# Power_PMIC.net
KiCad netlist of a schematic drawn in Altium Designer
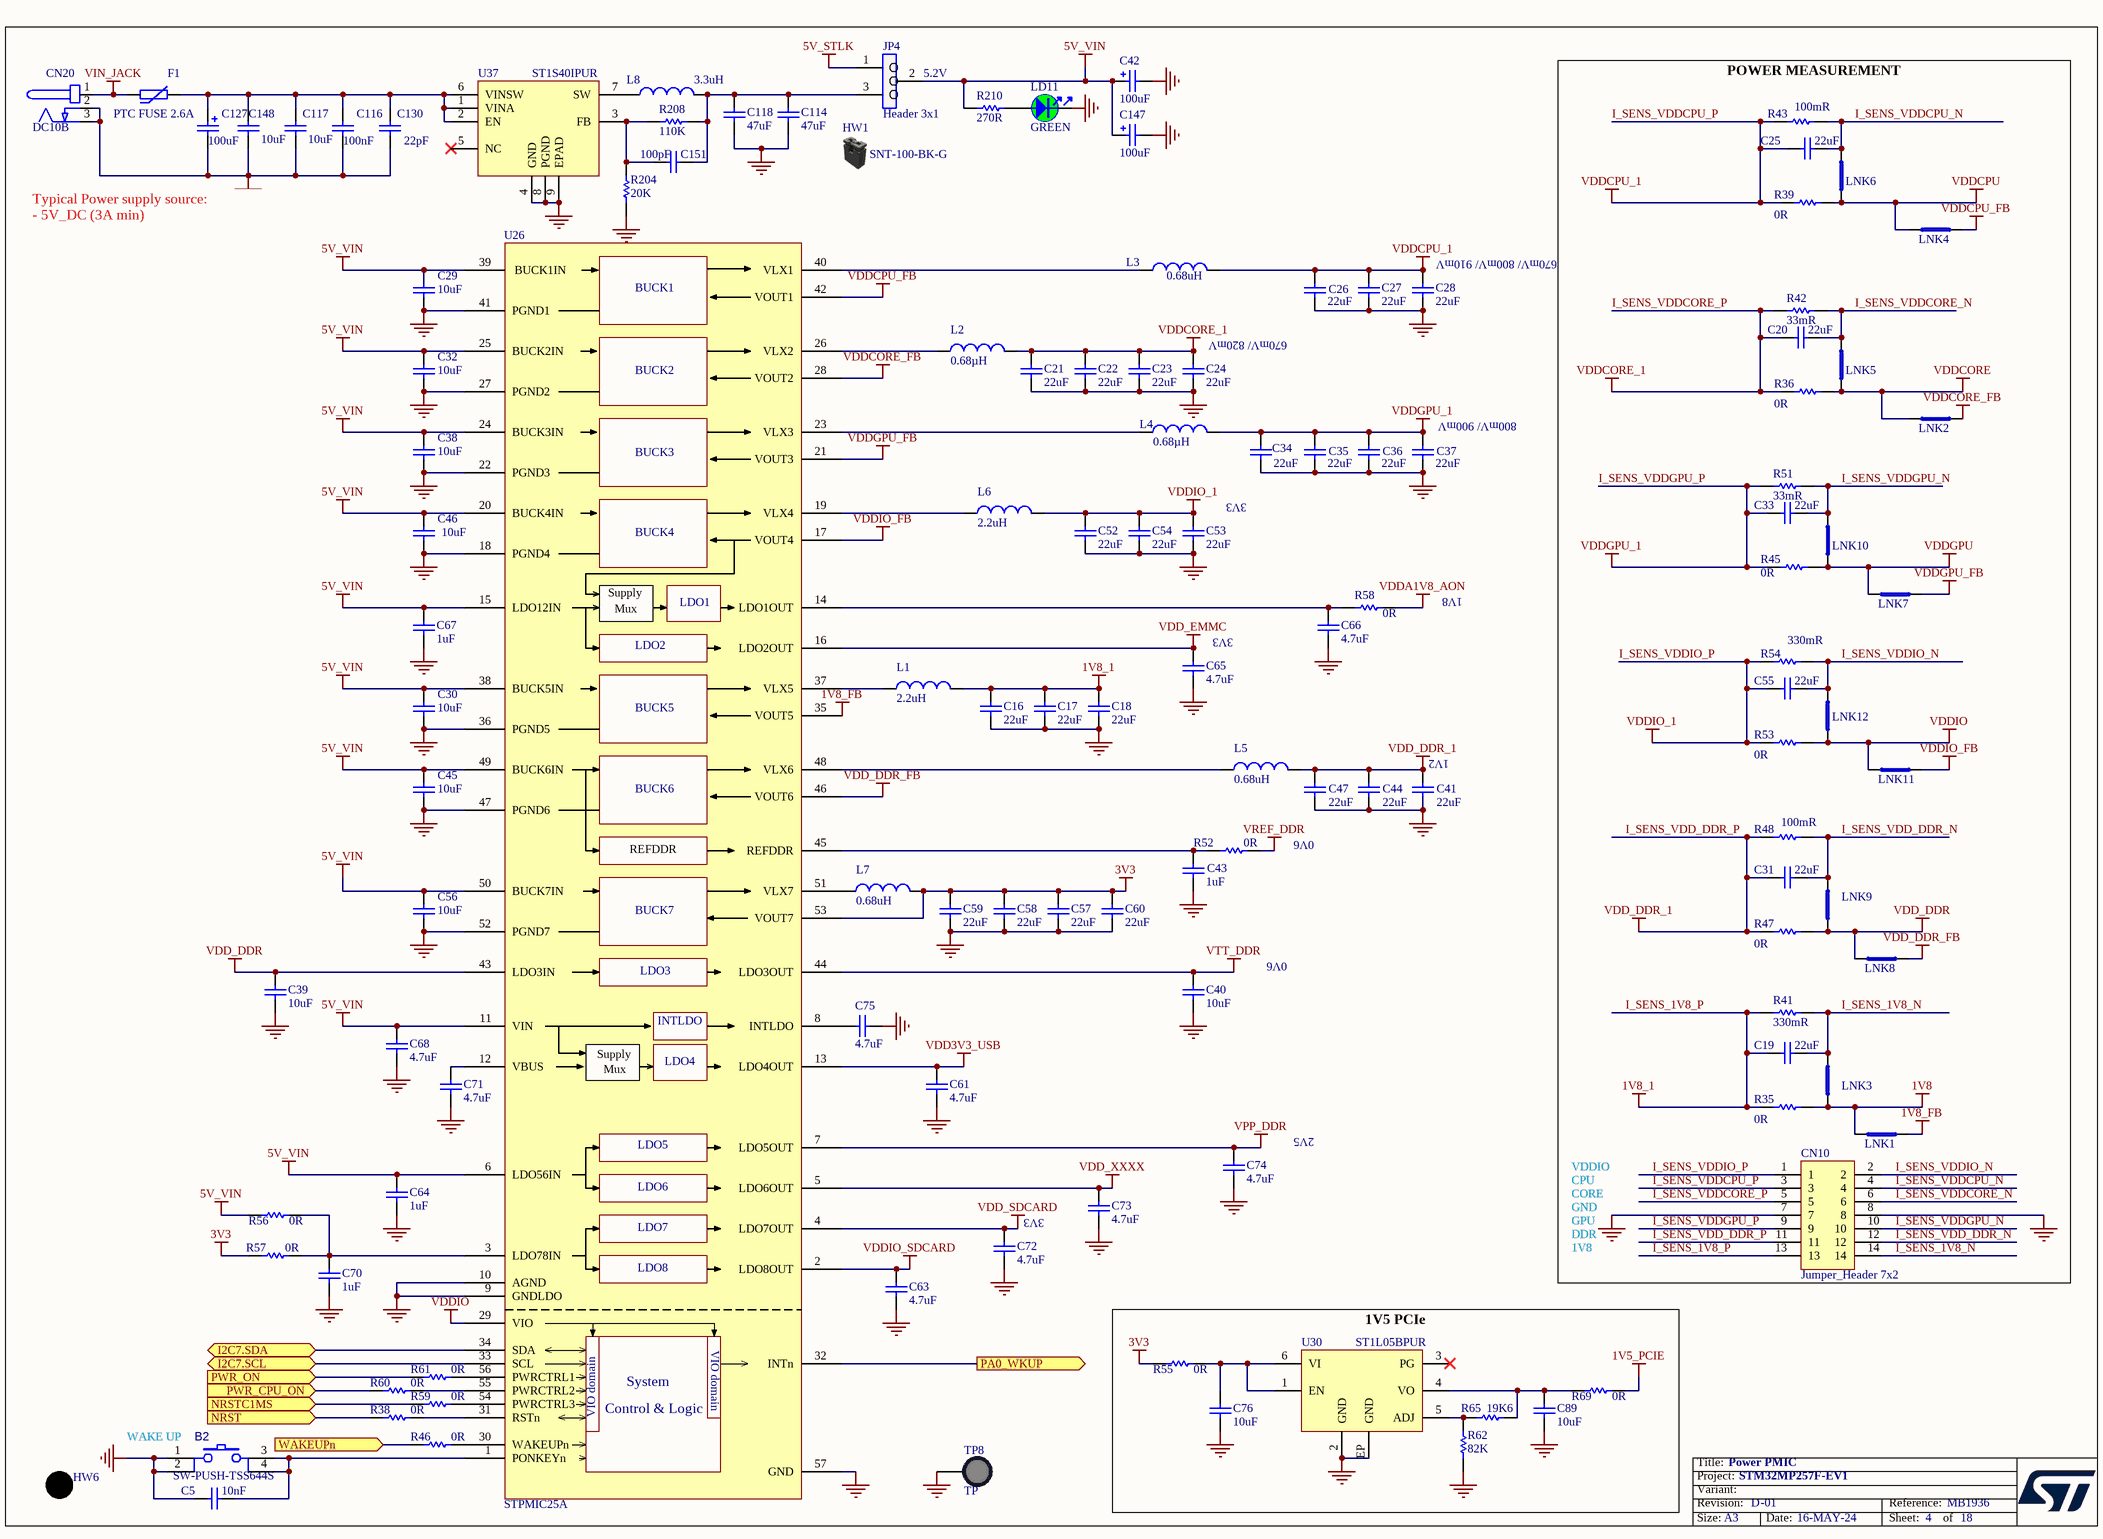
[diagram p0: Power_PMIC.SchDoc]

(export (version "E")
  (design (tool "Eeschema 10.0.6"))
  (components
    (comp (ref "B2")
      (value "SW-PUSH-TSS644S")
      (footprint "MCD_PARTS:SWI_KNITTER_TSS644S")
      (description "Push Button, NO, 0.05A, 12V, 2.6N, SMD, 9.0x6.2mm, T=7.3mm, changeable caps KTSC-6xx")
      (fields
        (field (name "INTERNAL_PART_NUMBER") "MCD-02417")
        (field (name "MANUFACTURER_PART_NUMBER") "TSS644S")
      )
      (libsource (lib "MCD_PARTS_database") (part "SW_PUSH_SMD"))
    )
    (comp (ref "C5")
      (value "10nF")
      (footprint "MCD_PARTS:C0402")
      (description "Capacitor, MLCC, 10nF, 50V, X7R, +/-10%, 0402, T=0.5mm")
      (fields
        (field (name "INTERNAL_PART_NUMBER") "MCD-02198")
        (field (name "MANUFACTURER_PART_NUMBER") "CC0402KRX7R9BB103")
      )
      (libsource (lib "MCD_PARTS_database") (part "Capacitor"))
    )
    (comp (ref "C16")
      (value "22uF")
      (footprint "MCD_PARTS:C0805")
      (description "Capacitor, MLCC, 22uF, 10V, X5R, +/-20%, 0805, T=1,25mm")
      (fields (field (name "INTERNAL_PART_NUMBER") "MCD-03139") (field (name "MANUFACTURER") "MURATA"))
      (libsource (lib "MCD_PARTS_database") (part "Capacitor"))
    )
    (comp (ref "C17")
      (value "22uF")
      (footprint "MCD_PARTS:C0805")
      (description "Capacitor, MLCC, 22uF, 10V, X5R, +/-20%, 0805, T=1,25mm")
      (fields (field (name "INTERNAL_PART_NUMBER") "MCD-03139") (field (name "MANUFACTURER") "MURATA"))
      (libsource (lib "MCD_PARTS_database") (part "Capacitor"))
    )
    (comp (ref "C18")
      (value "22uF")
      (footprint "MCD_PARTS:C0805")
      (description "Capacitor, MLCC, 22uF, 10V, X5R, +/-20%, 0805, T=1,25mm")
      (fields (field (name "INTERNAL_PART_NUMBER") "MCD-03139") (field (name "MANUFACTURER") "MURATA"))
      (libsource (lib "MCD_PARTS_database") (part "Capacitor"))
    )
    (comp (ref "C19")
      (value "22uF")
      (footprint "MCD_PARTS:C0603")
      (description "Capacitor, MLCC, 22uF, 6V3, X5R, +/-20%, 0603, T=0,8mm")
      (fields
        (field (name "INTERNAL_PART_NUMBER") "MCD-00100")
        (field (name "MANUFACTURER_PART_NUMBER") "GRM188R60J226MEA0J")
      )
      (libsource (lib "MCD_PARTS_database") (part "Capacitor"))
    )
    (comp (ref "C20")
      (value "22uF")
      (footprint "MCD_PARTS:C0603")
      (description "Capacitor, MLCC, 22uF, 6V3, X5R, +/-20%, 0603, T=0,8mm")
      (fields
        (field (name "INTERNAL_PART_NUMBER") "MCD-00100")
        (field (name "MANUFACTURER_PART_NUMBER") "GRM188R60J226MEA0J")
      )
      (libsource (lib "MCD_PARTS_database") (part "Capacitor"))
    )
    (comp (ref "C21")
      (value "22uF")
      (footprint "MCD_PARTS:C0603")
      (description "Capacitor, MLCC, 22uF, 6V3, X5R, +/-20%, 0603, T=0,8mm")
      (fields (field (name "INTERNAL_PART_NUMBER") "MCD-00100") (field (name "MANUFACTURER") "MURATA"))
      (libsource (lib "MCD_PARTS_database") (part "Capacitor"))
    )
    (comp (ref "C22")
      (value "22uF")
      (footprint "MCD_PARTS:C0603")
      (description "Capacitor, MLCC, 22uF, 6V3, X5R, +/-20%, 0603, T=0,8mm")
      (fields
        (field (name "INTERNAL_PART_NUMBER") "MCD-00100")
        (field (name "MANUFACTURER_PART_NUMBER") "GRM188R60J226MEA0J")
      )
      (libsource (lib "MCD_PARTS_database") (part "Capacitor"))
    )
    (comp (ref "C23")
      (value "22uF")
      (footprint "MCD_PARTS:C0603")
      (description "Capacitor, MLCC, 22uF, 6V3, X5R, +/-20%, 0603, T=0,8mm")
      (fields
        (field (name "INTERNAL_PART_NUMBER") "MCD-00100")
        (field (name "MANUFACTURER_PART_NUMBER") "GRM188R60J226MEA0J")
      )
      (libsource (lib "MCD_PARTS_database") (part "Capacitor"))
    )
    (comp (ref "C24")
      (value "22uF")
      (footprint "MCD_PARTS:C0603")
      (description "Capacitor, MLCC, 22uF, 6V3, X5R, +/-20%, 0603, T=0,8mm")
      (fields
        (field (name "INTERNAL_PART_NUMBER") "MCD-00100")
        (field (name "MANUFACTURER_PART_NUMBER") "GRM188R60J226MEA0J")
      )
      (libsource (lib "MCD_PARTS_database") (part "Capacitor"))
    )
    (comp (ref "C25")
      (value "22uF")
      (footprint "MCD_PARTS:C0603")
      (description "Capacitor, MLCC, 22uF, 6V3, X5R, +/-20%, 0603, T=0,8mm")
      (fields
        (field (name "INTERNAL_PART_NUMBER") "MCD-00100")
        (field (name "MANUFACTURER_PART_NUMBER") "GRM188R60J226MEA0J")
      )
      (libsource (lib "MCD_PARTS_database") (part "Capacitor"))
    )
    (comp (ref "C26")
      (value "22uF")
      (footprint "MCD_PARTS:C0603")
      (description "Capacitor, MLCC, 22uF, 6V3, X5R, +/-20%, 0603, T=0,8mm")
      (fields
        (field (name "INTERNAL_PART_NUMBER") "MCD-00100")
        (field (name "MANUFACTURER_PART_NUMBER") "GRM188R60J226MEA0J")
      )
      (libsource (lib "MCD_PARTS_database") (part "Capacitor"))
    )
    (comp (ref "C27")
      (value "22uF")
      (footprint "MCD_PARTS:C0603")
      (description "Capacitor, MLCC, 22uF, 6V3, X5R, +/-20%, 0603, T=0,8mm")
      (fields (field (name "INTERNAL_PART_NUMBER") "MCD-00100") (field (name "MANUFACTURER") "MURATA"))
      (libsource (lib "MCD_PARTS_database") (part "Capacitor"))
    )
    (comp (ref "C28")
      (value "22uF")
      (footprint "MCD_PARTS:C0603")
      (description "Capacitor, MLCC, 22uF, 6V3, X5R, +/-20%, 0603, T=0,8mm")
      (fields (field (name "INTERNAL_PART_NUMBER") "MCD-00100") (field (name "MANUFACTURER") "MURATA"))
      (libsource (lib "MCD_PARTS_database") (part "Capacitor"))
    )
    (comp (ref "C29")
      (value "10uF")
      (footprint "MCD_PARTS:C0603")
      (description "Capacitor, MLCC, 10uF, 10V, X5R, +/-10%, 0603, T=0,8mm")
      (fields
        (field (name "INTERNAL_PART_NUMBER") "MCD-00099")
        (field (name "MANUFACTURER_PART_NUMBER") "GRM188R61A106KE69D")
      )
      (libsource (lib "MCD_PARTS_database") (part "Capacitor"))
    )
    (comp (ref "C30")
      (value "10uF")
      (footprint "MCD_PARTS:C0603")
      (description "Capacitor, MLCC, 10uF, 10V, X5R, +/-10%, 0603, T=0,8mm")
      (fields
        (field (name "INTERNAL_PART_NUMBER") "MCD-00099")
        (field (name "MANUFACTURER_PART_NUMBER") "GRM188R61A106KE69D")
      )
      (libsource (lib "MCD_PARTS_database") (part "Capacitor"))
    )
    (comp (ref "C31")
      (value "22uF")
      (footprint "MCD_PARTS:C0603")
      (description "Capacitor, MLCC, 22uF, 6V3, X5R, +/-20%, 0603, T=0,8mm")
      (fields
        (field (name "INTERNAL_PART_NUMBER") "MCD-00100")
        (field (name "MANUFACTURER_PART_NUMBER") "GRM188R60J226MEA0J")
      )
      (libsource (lib "MCD_PARTS_database") (part "Capacitor"))
    )
    (comp (ref "C32")
      (value "10uF")
      (footprint "MCD_PARTS:C0603")
      (description "Capacitor, MLCC, 10uF, 10V, X5R, +/-10%, 0603, T=0,8mm")
      (fields
        (field (name "INTERNAL_PART_NUMBER") "MCD-00099")
        (field (name "MANUFACTURER_PART_NUMBER") "GRM188R61A106KE69D")
      )
      (libsource (lib "MCD_PARTS_database") (part "Capacitor"))
    )
    (comp (ref "C33")
      (value "22uF")
      (footprint "MCD_PARTS:C0603")
      (description "Capacitor, MLCC, 22uF, 6V3, X5R, +/-20%, 0603, T=0,8mm")
      (fields
        (field (name "INTERNAL_PART_NUMBER") "MCD-00100")
        (field (name "MANUFACTURER_PART_NUMBER") "GRM188R60J226MEA0J")
      )
      (libsource (lib "MCD_PARTS_database") (part "Capacitor"))
    )
    (comp (ref "C34")
      (value "22uF")
      (footprint "MCD_PARTS:C0603")
      (description "Capacitor, MLCC, 22uF, 6V3, X5R, +/-20%, 0603, T=0,8mm")
      (fields
        (field (name "INTERNAL_PART_NUMBER") "MCD-00100")
        (field (name "MANUFACTURER_PART_NUMBER") "GRM188R60J226MEA0J")
      )
      (libsource (lib "MCD_PARTS_database") (part "Capacitor"))
    )
    (comp (ref "C35")
      (value "22uF")
      (footprint "MCD_PARTS:C0603")
      (description "Capacitor, MLCC, 22uF, 6V3, X5R, +/-20%, 0603, T=0,8mm")
      (fields
        (field (name "INTERNAL_PART_NUMBER") "MCD-00100")
        (field (name "MANUFACTURER_PART_NUMBER") "GRM188R60J226MEA0J")
      )
      (libsource (lib "MCD_PARTS_database") (part "Capacitor"))
    )
    (comp (ref "C36")
      (value "22uF")
      (footprint "MCD_PARTS:C0603")
      (description "Capacitor, MLCC, 22uF, 6V3, X5R, +/-20%, 0603, T=0,8mm")
      (fields
        (field (name "INTERNAL_PART_NUMBER") "MCD-00100")
        (field (name "MANUFACTURER_PART_NUMBER") "GRM188R60J226MEA0J")
      )
      (libsource (lib "MCD_PARTS_database") (part "Capacitor"))
    )
    (comp (ref "C37")
      (value "22uF")
      (footprint "MCD_PARTS:C0603")
      (description "Capacitor, MLCC, 22uF, 6V3, X5R, +/-20%, 0603, T=0,8mm")
      (fields
        (field (name "INTERNAL_PART_NUMBER") "MCD-00100")
        (field (name "MANUFACTURER_PART_NUMBER") "GRM188R60J226MEA0J")
      )
      (libsource (lib "MCD_PARTS_database") (part "Capacitor"))
    )
    (comp (ref "C38")
      (value "10uF")
      (footprint "MCD_PARTS:C0603")
      (description "Capacitor, MLCC, 10uF, 10V, X5R, +/-10%, 0603, T=0,8mm")
      (fields
        (field (name "INTERNAL_PART_NUMBER") "MCD-00099")
        (field (name "MANUFACTURER_PART_NUMBER") "GRM188R61A106KE69D")
      )
      (libsource (lib "MCD_PARTS_database") (part "Capacitor"))
    )
    (comp (ref "C39")
      (value "10uF")
      (footprint "MCD_PARTS:C0402")
      (description "Capacitor, MLCC, 10uF, 6.3V, X5R, +/-20%, 0402, T=0.5mm")
      (fields (field (name "INTERNAL_PART_NUMBER") "MCD-03140") (field (name "MANUFACTURER") "MURATA"))
      (libsource (lib "MCD_PARTS_database") (part "Capacitor"))
    )
    (comp (ref "C40")
      (value "10uF")
      (footprint "MCD_PARTS:C0402")
      (description "Capacitor, MLCC, 10uF, 6.3V, X5R, +/-20%, 0402, T=0.5mm")
      (fields (field (name "INTERNAL_PART_NUMBER") "MCD-03140") (field (name "MANUFACTURER") "MURATA"))
      (libsource (lib "MCD_PARTS_database") (part "Capacitor"))
    )
    (comp (ref "C41")
      (value "22uF")
      (footprint "MCD_PARTS:C0603")
      (description "Capacitor, MLCC, 22uF, 6V3, X5R, +/-20%, 0603, T=0,8mm")
      (fields
        (field (name "INTERNAL_PART_NUMBER") "MCD-00100")
        (field (name "MANUFACTURER_PART_NUMBER") "GRM188R60J226MEA0J")
      )
      (libsource (lib "MCD_PARTS_database") (part "Capacitor"))
    )
    (comp (ref "C42")
      (value "100uF")
      (footprint "MCD_PARTS:CPOL_TCJ-B_1210_H210")
      (description "Capacitor, Tantalum, 100uF, 6V3, 40mR, +/-20%,  Type_B (3528 metric), T=1.9mm")
      (fields (field (name "INTERNAL_PART_NUMBER") "MCD-01796") (field (name "MANUFACTURER") "AVX"))
      (libsource (lib "MCD_PARTS_database") (part "Cap_POL_TANA"))
    )
    (comp (ref "C43")
      (value "1uF")
      (footprint "MCD_PARTS:C0402")
      (description "Capacitor, MLCC, 1uF, 10V, X5R, +/-10%, 0402, T=0.5mm")
      (fields (field (name "INTERNAL_PART_NUMBER") "MCD-01722") (field (name "MANUFACTURER") "YAGEO"))
      (libsource (lib "MCD_PARTS_database") (part "Capacitor"))
    )
    (comp (ref "C44")
      (value "22uF")
      (footprint "MCD_PARTS:C0603")
      (description "Capacitor, MLCC, 22uF, 6V3, X5R, +/-20%, 0603, T=0,8mm")
      (fields
        (field (name "INTERNAL_PART_NUMBER") "MCD-00100")
        (field (name "MANUFACTURER_PART_NUMBER") "GRM188R60J226MEA0J")
      )
      (libsource (lib "MCD_PARTS_database") (part "Capacitor"))
    )
    (comp (ref "C45")
      (value "10uF")
      (footprint "MCD_PARTS:C0603")
      (description "Capacitor, MLCC, 10uF, 10V, X5R, +/-10%, 0603, T=0,8mm")
      (fields
        (field (name "INTERNAL_PART_NUMBER") "MCD-00099")
        (field (name "MANUFACTURER_PART_NUMBER") "GRM188R61A106KE69D")
      )
      (libsource (lib "MCD_PARTS_database") (part "Capacitor"))
    )
    (comp (ref "C46")
      (value "10uF")
      (footprint "MCD_PARTS:C0603")
      (description "Capacitor, MLCC, 10uF, 10V, X5R, +/-10%, 0603, T=0,8mm")
      (fields
        (field (name "INTERNAL_PART_NUMBER") "MCD-00099")
        (field (name "MANUFACTURER_PART_NUMBER") "GRM188R61A106KE69D")
      )
      (libsource (lib "MCD_PARTS_database") (part "Capacitor"))
    )
    (comp (ref "C47")
      (value "22uF")
      (footprint "MCD_PARTS:C0603")
      (description "Capacitor, MLCC, 22uF, 6V3, X5R, +/-20%, 0603, T=0,8mm")
      (fields
        (field (name "INTERNAL_PART_NUMBER") "MCD-00100")
        (field (name "MANUFACTURER_PART_NUMBER") "GRM188R60J226MEA0J")
      )
      (libsource (lib "MCD_PARTS_database") (part "Capacitor"))
    )
    (comp (ref "C52")
      (value "22uF")
      (footprint "MCD_PARTS:C0805")
      (description "Capacitor, MLCC, 22uF, 10V, X5R, +/-20%, 0805, T=1,25mm")
      (fields (field (name "INTERNAL_PART_NUMBER") "MCD-03139") (field (name "MANUFACTURER") "MURATA"))
      (libsource (lib "MCD_PARTS_database") (part "Capacitor"))
    )
    (comp (ref "C53")
      (value "22uF")
      (footprint "MCD_PARTS:C0805")
      (description "Capacitor, MLCC, 22uF, 10V, X5R, +/-20%, 0805, T=1,25mm")
      (fields (field (name "INTERNAL_PART_NUMBER") "MCD-03139") (field (name "MANUFACTURER") "MURATA"))
      (libsource (lib "MCD_PARTS_database") (part "Capacitor"))
    )
    (comp (ref "C54")
      (value "22uF")
      (footprint "MCD_PARTS:C0805")
      (description "Capacitor, MLCC, 22uF, 10V, X5R, +/-20%, 0805, T=1,25mm")
      (fields (field (name "INTERNAL_PART_NUMBER") "MCD-03139") (field (name "MANUFACTURER") "MURATA"))
      (libsource (lib "MCD_PARTS_database") (part "Capacitor"))
    )
    (comp (ref "C55")
      (value "22uF")
      (footprint "MCD_PARTS:C0603")
      (description "Capacitor, MLCC, 22uF, 6V3, X5R, +/-20%, 0603, T=0,8mm")
      (fields
        (field (name "INTERNAL_PART_NUMBER") "MCD-00100")
        (field (name "MANUFACTURER_PART_NUMBER") "GRM188R60J226MEA0J")
      )
      (libsource (lib "MCD_PARTS_database") (part "Capacitor"))
    )
    (comp (ref "C56")
      (value "10uF")
      (footprint "MCD_PARTS:C0603")
      (description "Capacitor, MLCC, 10uF, 10V, X5R, +/-10%, 0603, T=0,8mm")
      (fields
        (field (name "INTERNAL_PART_NUMBER") "MCD-00099")
        (field (name "MANUFACTURER_PART_NUMBER") "GRM188R61A106KE69D")
      )
      (libsource (lib "MCD_PARTS_database") (part "Capacitor"))
    )
    (comp (ref "C57")
      (value "22uF")
      (footprint "MCD_PARTS:C0805")
      (description "Capacitor, MLCC, 22uF, 10V, X5R, +/-20%, 0805, T=1,25mm")
      (fields (field (name "INTERNAL_PART_NUMBER") "MCD-03139") (field (name "MANUFACTURER") "MURATA"))
      (libsource (lib "MCD_PARTS_database") (part "Capacitor"))
    )
    (comp (ref "C58")
      (value "22uF")
      (footprint "MCD_PARTS:C0805")
      (description "Capacitor, MLCC, 22uF, 10V, X5R, +/-20%, 0805, T=1,25mm")
      (fields (field (name "INTERNAL_PART_NUMBER") "MCD-03139") (field (name "MANUFACTURER") "MURATA"))
      (libsource (lib "MCD_PARTS_database") (part "Capacitor"))
    )
    (comp (ref "C59")
      (value "22uF")
      (footprint "MCD_PARTS:C0805")
      (description "Capacitor, MLCC, 22uF, 10V, X5R, +/-20%, 0805, T=1,25mm")
      (fields (field (name "INTERNAL_PART_NUMBER") "MCD-03139") (field (name "MANUFACTURER") "MURATA"))
      (libsource (lib "MCD_PARTS_database") (part "Capacitor"))
    )
    (comp (ref "C60")
      (value "22uF")
      (footprint "MCD_PARTS:C0805")
      (description "Capacitor, MLCC, 22uF, 10V, X5R, +/-20%, 0805, T=1,25mm")
      (fields (field (name "INTERNAL_PART_NUMBER") "MCD-03139") (field (name "MANUFACTURER") "MURATA"))
      (libsource (lib "MCD_PARTS_database") (part "Capacitor"))
    )
    (comp (ref "C61")
      (value "4.7uF")
      (footprint "MCD_PARTS:C0402")
      (description "Capacitor, MLCC, 4.7uF, 6V3, X5R, +/-20%, 0402, T=0.5mm")
      (fields
        (field (name "INTERNAL_PART_NUMBER") "MCD-01356")
        (field (name "MANUFACTURER_PART_NUMBER") "GRM155R60J475ME47")
      )
      (libsource (lib "MCD_PARTS_database") (part "Capacitor"))
    )
    (comp (ref "C63")
      (value "4.7uF")
      (footprint "MCD_PARTS:C0402")
      (description "Capacitor, MLCC, 4.7uF, 6V3, X5R, +/-20%, 0402, T=0.5mm")
      (fields
        (field (name "INTERNAL_PART_NUMBER") "MCD-01356")
        (field (name "MANUFACTURER_PART_NUMBER") "GRM155R60J475ME47")
      )
      (libsource (lib "MCD_PARTS_database") (part "Capacitor"))
    )
    (comp (ref "C64")
      (value "1uF")
      (footprint "MCD_PARTS:C0402")
      (description "Capacitor, MLCC, 1uF, 25V, X5R, +/-10%, 0402, T=0.5mm")
      (fields (field (name "INTERNAL_PART_NUMBER") "MCD-00095") (field (name "MANUFACTURER") "MURATA"))
      (libsource (lib "MCD_PARTS_database") (part "Capacitor"))
    )
    (comp (ref "C65")
      (value "4.7uF")
      (footprint "MCD_PARTS:C0402")
      (description "Capacitor, MLCC, 4.7uF, 6V3, X5R, +/-20%, 0402, T=0.5mm")
      (fields
        (field (name "INTERNAL_PART_NUMBER") "MCD-01356")
        (field (name "MANUFACTURER_PART_NUMBER") "GRM155R60J475ME47")
      )
      (libsource (lib "MCD_PARTS_database") (part "Capacitor"))
    )
    (comp (ref "C66")
      (value "4.7uF")
      (footprint "MCD_PARTS:C0402")
      (description "Capacitor, MLCC, 4.7uF, 6V3, X5R, +/-20%, 0402, T=0.5mm")
      (fields
        (field (name "INTERNAL_PART_NUMBER") "MCD-01356")
        (field (name "MANUFACTURER_PART_NUMBER") "GRM155R60J475ME47")
      )
      (libsource (lib "MCD_PARTS_database") (part "Capacitor"))
    )
    (comp (ref "C67")
      (value "1uF")
      (footprint "MCD_PARTS:C0402")
      (description "Capacitor, MLCC, 1uF, 25V, X5R, +/-10%, 0402, T=0.5mm")
      (fields (field (name "INTERNAL_PART_NUMBER") "MCD-00095") (field (name "MANUFACTURER") "MURATA"))
      (libsource (lib "MCD_PARTS_database") (part "Capacitor"))
    )
    (comp (ref "C68")
      (value "4.7uF")
      (footprint "MCD_PARTS:C0402")
      (description "Capacitor, MLCC, 4.7uF, 6V3, X5R, +/-20%, 0402, T=0.5mm")
      (fields
        (field (name "INTERNAL_PART_NUMBER") "MCD-01356")
        (field (name "MANUFACTURER_PART_NUMBER") "GRM155R60J475ME47")
      )
      (libsource (lib "MCD_PARTS_database") (part "Capacitor"))
    )
    (comp (ref "C70")
      (value "1uF")
      (footprint "MCD_PARTS:C0402")
      (description "Capacitor, MLCC, 1uF, 25V, X5R, +/-10%, 0402, T=0.5mm")
      (fields (field (name "INTERNAL_PART_NUMBER") "MCD-00095") (field (name "MANUFACTURER") "MURATA"))
      (libsource (lib "MCD_PARTS_database") (part "Capacitor"))
    )
    (comp (ref "C71")
      (value "4.7uF")
      (footprint "MCD_PARTS:C0603")
      (description "Capacitor, MLCC, 4.7uF, 16V, X5R, +/-20%, 0603, T=0.8mm")
      (fields (field (name "INTERNAL_PART_NUMBER") "MCD-00097") (field (name "MANUFACTURER") "MURATA"))
      (libsource (lib "MCD_PARTS_database") (part "Capacitor"))
    )
    (comp (ref "C72")
      (value "4.7uF")
      (footprint "MCD_PARTS:C0402")
      (description "Capacitor, MLCC, 4.7uF, 6V3, X5R, +/-20%, 0402, T=0.5mm")
      (fields
        (field (name "INTERNAL_PART_NUMBER") "MCD-01356")
        (field (name "MANUFACTURER_PART_NUMBER") "GRM155R60J475ME47")
      )
      (libsource (lib "MCD_PARTS_database") (part "Capacitor"))
    )
    (comp (ref "C73")
      (value "4.7uF")
      (footprint "MCD_PARTS:C0402")
      (description "Capacitor, MLCC, 4.7uF, 6V3, X5R, +/-20%, 0402, T=0.5mm")
      (fields
        (field (name "INTERNAL_PART_NUMBER") "MCD-01356")
        (field (name "MANUFACTURER_PART_NUMBER") "GRM155R60J475ME47")
      )
      (libsource (lib "MCD_PARTS_database") (part "Capacitor"))
    )
    (comp (ref "C74")
      (value "4.7uF")
      (footprint "MCD_PARTS:C0402")
      (description "Capacitor, MLCC, 4.7uF, 6V3, X5R, +/-20%, 0402, T=0.5mm")
      (fields
        (field (name "INTERNAL_PART_NUMBER") "MCD-01356")
        (field (name "MANUFACTURER_PART_NUMBER") "GRM155R60J475ME47")
      )
      (libsource (lib "MCD_PARTS_database") (part "Capacitor"))
    )
    (comp (ref "C75")
      (value "4.7uF")
      (footprint "MCD_PARTS:C0402")
      (description "Capacitor, MLCC, 4.7uF, 6V3, X5R, +/-20%, 0402, T=0.5mm")
      (fields
        (field (name "INTERNAL_PART_NUMBER") "MCD-01356")
        (field (name "MANUFACTURER_PART_NUMBER") "GRM155R60J475ME47")
      )
      (libsource (lib "MCD_PARTS_database") (part "Capacitor"))
    )
    (comp (ref "C76")
      (value "10uF")
      (footprint "MCD_PARTS:C0603")
      (description "Capacitor, MLCC, 10uF, 10V, X5R, +/-10%, 0603, T=0.8mm")
      (fields (field (name "INTERNAL_PART_NUMBER") "MCD-00099") (field (name "MANUFACTURER") "MURATA"))
      (libsource (lib "MCD_PARTS_database") (part "Capacitor"))
    )
    (comp (ref "C89")
      (value "10uF")
      (footprint "MCD_PARTS:C0603")
      (description "Capacitor, MLCC, 10uF, 10V, X5R, +/-10%, 0603, T=0.8mm")
      (fields (field (name "INTERNAL_PART_NUMBER") "MCD-00099") (field (name "MANUFACTURER") "MURATA"))
      (libsource (lib "MCD_PARTS_database") (part "Capacitor"))
    )
    (comp (ref "C114")
      (value "47uF")
      (footprint "MCD_PARTS:C0805")
      (description "Capacitor, MLCC, 47uF, 10V, X5R, +/-20%, 0805, T=1,25mm")
      (fields (field (name "INTERNAL_PART_NUMBER") "MCD-00204") (field (name "MANUFACTURER") "MURATA"))
      (libsource (lib "MCD_PARTS_database") (part "Capacitor"))
    )
    (comp (ref "C116")
      (value "100nF")
      (footprint "MCD_PARTS:C0805_H0P85")
      (description "Capacitor, MLCC, 100nF, 50V, X7R, 10%, 0805, T=0,85mm")
      (fields (field (name "INTERNAL_PART_NUMBER") "MCD-01525") (field (name "BMS_PART_NUMBER") "9142249"))
      (libsource (lib "MCD_PARTS_database") (part "Capacitor"))
    )
    (comp (ref "C117")
      (value "10uF")
      (footprint "MCD_PARTS:C0805")
      (description "Capacitor, MLCC, 10uF, 25V, X5R, +/-10%, 0805, T=0,85mm")
      (fields (field (name "INTERNAL_PART_NUMBER") "MCD-00014") (field (name "MANUFACTURER") "YAGEO"))
      (libsource (lib "MCD_PARTS_database") (part "Capacitor"))
    )
    (comp (ref "C118")
      (value "47uF")
      (footprint "MCD_PARTS:C0805")
      (description "Capacitor, MLCC, 47uF, 10V, X5R, +/-20%, 0805, T=1,25mm")
      (fields (field (name "INTERNAL_PART_NUMBER") "MCD-00204") (field (name "MANUFACTURER") "MURATA"))
      (libsource (lib "MCD_PARTS_database") (part "Capacitor"))
    )
    (comp (ref "C127")
      (value "100uF")
      (footprint "MCD_PARTS:CPOL_WURTH_WCAP-ASLL_8X10P5")
      (description "Capacitor,Electrolytic,100uF,35V, 20%, SMT, D=8mm, T=10.5mm")
      (fields
        (field (name "INTERNAL_PART_NUMBER") "MCD-01683")
        (field (name "MANUFACTURER") "WURTH ELEKTRONIK")
      )
      (libsource (lib "MCD_PARTS_database") (part "Cap_POL_TANA"))
    )
    (comp (ref "C130")
      (value "22pF")
      (footprint "MCD_PARTS:C0402")
      (description "Capacitor, MLCC, 22pF, 50V, C0G, 5%, 0402, T=0,5mm")
      (fields (field (name "INTERNAL_PART_NUMBER") "MCD-01995") (field (name "MANUFACTURER") "TDK"))
      (libsource (lib "MCD_PARTS_database") (part "Capacitor"))
    )
    (comp (ref "C147")
      (value "100uF")
      (footprint "MCD_PARTS:CPOL_TCJ-B_1210_H210")
      (description "Capacitor, Tantalum, 100uF, 6V3, 40mR, +/-20%,  Type_B (3528 metric), T=1.9mm")
      (fields (field (name "INTERNAL_PART_NUMBER") "MCD-01796") (field (name "MANUFACTURER") "AVX"))
      (libsource (lib "MCD_PARTS_database") (part "Cap_POL_TANA"))
    )
    (comp (ref "C148")
      (value "10uF")
      (footprint "MCD_PARTS:C0805")
      (description "Capacitor, MLCC, 10uF, 25V, X5R, +/-10%, 0805, T=0,85mm")
      (fields (field (name "INTERNAL_PART_NUMBER") "MCD-00014") (field (name "MANUFACTURER") "YAGEO"))
      (libsource (lib "MCD_PARTS_database") (part "Capacitor"))
    )
    (comp (ref "C151")
      (value "100pF")
      (footprint "MCD_PARTS:C0402")
      (description "Capacitor,MLCC,100pF,50V,NPO,+/-5%,0402,T=0,5mm")
      (fields
        (field (name "INTERNAL_PART_NUMBER") "MCD-00205")
        (field (name "MANUFACTURER_PART_NUMBER") "CC0402JRNPO9BN101")
      )
      (libsource (lib "MCD_PARTS_database") (part "Capacitor"))
    )
    (comp (ref "CN10")
      (value "Jumper_Header 7x2")
      (footprint "MCD_PARTS:CON_SAMTEC_TSW-107-07-X-D")
      (description "Header, 7x2, 2,54mm, VR, TH, Height 5.84mm/2.54mm")
      (fields (field (name "INTERNAL_PART_NUMBER") "MCD-02123") (field (name "MANUFACTURER") "SAMTEC"))
      (libsource (lib "MCD_PARTS_database") (part "Header 7x2"))
    )
    (comp (ref "CN20")
      (value "DC10B")
      (footprint "MCD_PARTS:CON_DC-POWER-SOCKET_CLIFF_FC68149_DC10B")
      (description "DC-Power-Jack, 2.5mm, 5A, RA, TH")
      (fields (field (name "INTERNAL_PART_NUMBER") "MCD-00173") (field (name "BMS_PART_NUMBER") "9087803"))
      (libsource (lib "MCD_PARTS_database") (part "Power_Jack_DC10B"))
    )
    (comp (ref "F1")
      (value "PTC FUSE 2.6A")
      (footprint "MCD_PARTS:PTC_BEL-FUSE_1812_0ZCG0260FF2C")
      (description "SMD, PTC resettable fuse, IH:2.6A, IT:5A, Vdc_max:8V, Rmax:47mohm, BELFUSE")
      (fields (field (name "INTERNAL_PART_NUMBER") "MCD-00624") (field (name "MANUFACTURER") "BELFUSE"))
      (libsource (lib "MCD_PARTS_database") (part "0ZCG0260FF2C"))
    )
    (comp (ref "HW1")
      (value "SNT-100-BK-G")
      (description "SHUNT 2.54mm BLACK")
      (fields (field (name "INTERNAL_PART_NUMBER") "MCD-00043") (field (name "MANUFACTURER") "SAMTEC"))
      (libsource (lib "MCD_PARTS_database") (part "Shunt Black 2.54mm"))
    )
    (comp (ref "HW6")
      (value "SW-CAP-KTSC-62K")
      (description "Black round cap for TSS6x series")
      (fields
        (field (name "INTERNAL_PART_NUMBER") "MCD-02420")
        (field (name "MANUFACTURER") "KNITTER-SWITCH")
      )
      (libsource (lib "MCD_PARTS_database") (part "SW-CAP-Black"))
    )
    (comp (ref "JP4")
      (value "Header 3x1")
      (footprint "MCD_PARTS:CON_SAMTEC_TSW-103-07-F-S")
      (description "Header, 3x1, 2.54mm, VR, TH, T=5.84mm/2.54mm")
      (fields (field (name "INTERNAL_PART_NUMBER") "MCD-00111") (field (name "MANUFACTURER") "SAMTEC"))
      (libsource (lib "MCD_PARTS_database") (part "Jumper_Header 3x1"))
    )
    (comp (ref "L1")
      (value "2.2uH")
      (footprint "MCD_PARTS:IND_2016_MURATA_LQM2MPN2R2NG0")
      (description "Inductor, 2.2uH, +/-20%, Itemp= 1700mA, Isat= 2400mA, 0R140, 0806, T=1mm")
      (fields (field (name "INTERNAL_PART_NUMBER") "MCD-03143") (field (name "MANUFACTURER") "MURATA"))
      (libsource (lib "MCD_PARTS_database") (part "Inductor"))
    )
    (comp (ref "L2")
      (value "0.68µH")
      (footprint "MCD_PARTS:IND_2520_TOKO_DFE252012P")
      (description "Inductor, 0.68uH, +/-20%, Itemp= 3900mA, Isat= 5400mA, 0R031, 1008, T=1.2mm")
      (fields (field (name "INTERNAL_PART_NUMBER") "MCD-03142") (field (name "MANUFACTURER") "MURATA"))
      (libsource (lib "MCD_PARTS_database") (part "Inductor"))
    )
    (comp (ref "L3")
      (value "0.68uH")
      (footprint "MCD_PARTS:IND_2016_MURATA_LQM2MPN2R2NG0")
      (description "Inductor, 0.68uH, +/-20%, Itemp= 3100mA, Isat= 4300mA, 0R043, 0806, T=1mm")
      (fields (field (name "INTERNAL_PART_NUMBER") "MCD-03141") (field (name "MANUFACTURER") "MURATA"))
      (libsource (lib "MCD_PARTS_database") (part "Inductor"))
    )
    (comp (ref "L4")
      (value "0.68µH")
      (footprint "MCD_PARTS:IND_2520_TOKO_DFE252012P")
      (description "Inductor, 0.68uH, +/-20%, Itemp= 3900mA, Isat= 5400mA, 0R031, 1008, T=1.2mm")
      (fields (field (name "INTERNAL_PART_NUMBER") "MCD-03142") (field (name "MANUFACTURER") "MURATA"))
      (libsource (lib "MCD_PARTS_database") (part "Inductor"))
    )
    (comp (ref "L5")
      (value "0.68uH")
      (footprint "MCD_PARTS:IND_2016_MURATA_LQM2MPN2R2NG0")
      (description "Inductor, 0.68uH, +/-20%, Itemp= 3100mA, Isat= 4300mA, 0R043, 0806, T=1mm")
      (fields (field (name "INTERNAL_PART_NUMBER") "MCD-03141") (field (name "MANUFACTURER") "MURATA"))
      (libsource (lib "MCD_PARTS_database") (part "Inductor"))
    )
    (comp (ref "L6")
      (value "2.2uH")
      (footprint "MCD_PARTS:IND_2016_MURATA_LQM2MPN2R2NG0")
      (description "Inductor, 2.2uH, +/-20%, Itemp= 1700mA, Isat= 2400mA, 0R140, 0806, T=1mm")
      (fields (field (name "INTERNAL_PART_NUMBER") "MCD-03143") (field (name "MANUFACTURER") "MURATA"))
      (libsource (lib "MCD_PARTS_database") (part "Inductor"))
    )
    (comp (ref "L7")
      (value "0.68uH")
      (footprint "MCD_PARTS:IND_2016_MURATA_LQM2MPN2R2NG0")
      (description "Inductor, 0.68uH, +/-20%, Itemp= 3100mA, Isat= 4300mA, 0R043, 0806, T=1mm")
      (fields (field (name "INTERNAL_PART_NUMBER") "MCD-03141") (field (name "MANUFACTURER") "MURATA"))
      (libsource (lib "MCD_PARTS_database") (part "Inductor"))
    )
    (comp (ref "L8")
      (value "3.3uH")
      (footprint "MCD_PARTS:IND_5040_WURTH_74404054033")
      (description "Fixed Inductors WE-LQS 5040 3.3uH 3.4A 24mOhm")
      (fields
        (field (name "INTERNAL_PART_NUMBER") "MCD-02220")
        (field (name "MANUFACTURER") "WURTH ELEKTRONIK")
      )
      (libsource (lib "MCD_PARTS_database") (part "Inductor"))
    )
    (comp (ref "LD11")
      (value "GREEN")
      (footprint "MCD_PARTS:LED_0603_OSRAM_LG-Q396-PS-35_GREEN_1A2K_H0P4")
      (description "LED Green, 0603 SMD, Forward Voltage Typ=2V, Max=2.5V")
      (fields
        (field (name "INTERNAL_PART_NUMBER") "MCD-00588")
        (field (name "MANUFACTURER_PART_NUMBER") "LG Q396-PS-35")
        (field (name "PROVIDED_BY") "SUBCO")
      )
      (libsource (lib "MCD_PARTS_database") (part "LED_green"))
    )
    (comp (ref "LNK1")
      (value "link_200")
      (footprint "MCD_PARTS:LINK200")
      (description "link 0.2mm")
      (libsource (lib "MCD_Temp_LBE") (part "link_200"))
    )
    (comp (ref "LNK2")
      (value "link_200")
      (footprint "MCD_PARTS:LINK200")
      (description "link 0.2mm")
      (libsource (lib "MCD_Temp_LBE") (part "link_200"))
    )
    (comp (ref "LNK3")
      (value "link_200")
      (footprint "MCD_PARTS:LINK200")
      (description "link 0.2mm")
      (libsource (lib "MCD_Temp_LBE") (part "link_200"))
    )
    (comp (ref "LNK4")
      (value "link_200")
      (footprint "MCD_PARTS:LINK200")
      (description "link 0.2mm")
      (libsource (lib "MCD_Temp_LBE") (part "link_200"))
    )
    (comp (ref "LNK5")
      (value "link_200")
      (footprint "MCD_PARTS:LINK200")
      (description "link 0.2mm")
      (libsource (lib "MCD_Temp_LBE") (part "link_200"))
    )
    (comp (ref "LNK6")
      (value "link_200")
      (footprint "MCD_PARTS:LINK200")
      (description "link 0.2mm")
      (libsource (lib "MCD_Temp_LBE") (part "link_200"))
    )
    (comp (ref "LNK7")
      (value "link_200")
      (footprint "MCD_PARTS:LINK200")
      (description "link 0.2mm")
      (libsource (lib "MCD_Temp_LBE") (part "link_200"))
    )
    (comp (ref "LNK8")
      (value "link_200")
      (footprint "MCD_PARTS:LINK200")
      (description "link 0.2mm")
      (libsource (lib "MCD_Temp_LBE") (part "link_200"))
    )
    (comp (ref "LNK9")
      (value "link_200")
      (footprint "MCD_PARTS:LINK200")
      (description "link 0.2mm")
      (libsource (lib "MCD_Temp_LBE") (part "link_200"))
    )
    (comp (ref "LNK10")
      (value "link_200")
      (footprint "MCD_PARTS:LINK200")
      (description "link 0.2mm")
      (libsource (lib "MCD_Temp_LBE") (part "link_200"))
    )
    (comp (ref "LNK11")
      (value "link_200")
      (footprint "MCD_PARTS:LINK200")
      (description "link 0.2mm")
      (libsource (lib "MCD_Temp_LBE") (part "link_200"))
    )
    (comp (ref "LNK12")
      (value "link_200")
      (footprint "MCD_PARTS:LINK200")
      (description "link 0.2mm")
      (libsource (lib "MCD_Temp_LBE") (part "link_200"))
    )
    (comp (ref "R35")
      (value "0R")
      (footprint "MCD_PARTS:R0603")
      (description "Resistor,0R,0603,ULO")
      (fields
        (field (name "INTERNAL_PART_NUMBER") "MCD-00181")
        (field (name "MANUFACTURER_PART_NUMBER") "PMR03EZPJ000")
        (field (name "PROVIDED_BY") "SUBCO")
      )
      (libsource (lib "MCD_PARTS_database") (part "Resistor"))
    )
    (comp (ref "R36")
      (value "0R")
      (footprint "MCD_PARTS:R0603")
      (description "Resistor,0R,0603,ULO")
      (fields
        (field (name "INTERNAL_PART_NUMBER") "MCD-00181")
        (field (name "MANUFACTURER_PART_NUMBER") "PMR03EZPJ000")
        (field (name "PROVIDED_BY") "SUBCO")
      )
      (libsource (lib "MCD_PARTS_database") (part "Resistor"))
    )
    (comp (ref "R38")
      (value "0R")
      (footprint "MCD_PARTS:R0402")
      (description "Resistor,0R,0402,5%,1/16W")
      (fields
        (field (name "INTERNAL_PART_NUMBER") "MCD-00052")
        (field (name "MANUFACTURER_PART_NUMBER") "RC0402JR-070RL")
        (field (name "PROVIDED_BY") "SUBCO")
      )
      (libsource (lib "MCD_PARTS_database") (part "Resistor"))
    )
    (comp (ref "R39")
      (value "0R")
      (footprint "MCD_PARTS:R0603")
      (description "Resistor,0R,0603,ULO")
      (fields
        (field (name "INTERNAL_PART_NUMBER") "MCD-00181")
        (field (name "MANUFACTURER_PART_NUMBER") "PMR03EZPJ000")
        (field (name "PROVIDED_BY") "SUBCO")
      )
      (libsource (lib "MCD_PARTS_database") (part "Resistor"))
    )
    (comp (ref "R41")
      (value "330mR")
      (footprint "MCD_PARTS:R0603")
      (description "Resistor, 330mR, 0603, +/-1%, 1/5W")
      (fields (field (name "INTERNAL_PART_NUMBER") "MCD-03197") (field (name "MANUFACTURER") "YAGEO"))
      (libsource (lib "MCD_PARTS_database") (part "Resistor"))
    )
    (comp (ref "R42")
      (value "33mR")
      (footprint "MCD_PARTS:R0603")
      (description "Resistor, 33mR, 0603, +/-1%, 1/4W")
      (fields (field (name "INTERNAL_PART_NUMBER") "MCD-03229") (field (name "MANUFACTURER") "PANASONIC"))
      (libsource (lib "MCD_PARTS_database") (part "Resistor"))
    )
    (comp (ref "R43")
      (value "100mR")
      (footprint "MCD_PARTS:R0603")
      (description "Resistor,100moHm,0603,1%,1/3W")
      (fields (field (name "INTERNAL_PART_NUMBER") "MCD-02234") (field (name "MANUFACTURER") "PANASONIC"))
      (libsource (lib "MCD_PARTS_database") (part "Resistor"))
    )
    (comp (ref "R45")
      (value "0R")
      (footprint "MCD_PARTS:R0603")
      (description "Resistor,0R,0603,ULO")
      (fields
        (field (name "INTERNAL_PART_NUMBER") "MCD-00181")
        (field (name "MANUFACTURER_PART_NUMBER") "PMR03EZPJ000")
        (field (name "PROVIDED_BY") "SUBCO")
      )
      (libsource (lib "MCD_PARTS_database") (part "Resistor"))
    )
    (comp (ref "R46")
      (value "0R")
      (footprint "MCD_PARTS:R0402")
      (description "Resistor,0R,0402,5%,1/16W")
      (fields
        (field (name "INTERNAL_PART_NUMBER") "MCD-00052")
        (field (name "MANUFACTURER_PART_NUMBER") "RC0402JR-070RL")
        (field (name "PROVIDED_BY") "SUBCO")
      )
      (libsource (lib "MCD_PARTS_database") (part "Resistor"))
    )
    (comp (ref "R47")
      (value "0R")
      (footprint "MCD_PARTS:R0603")
      (description "Resistor,0R,0603,ULO")
      (fields
        (field (name "INTERNAL_PART_NUMBER") "MCD-00181")
        (field (name "MANUFACTURER_PART_NUMBER") "PMR03EZPJ000")
        (field (name "PROVIDED_BY") "SUBCO")
      )
      (libsource (lib "MCD_PARTS_database") (part "Resistor"))
    )
    (comp (ref "R48")
      (value "100mR")
      (footprint "MCD_PARTS:R0603")
      (description "Resistor,100moHm,0603,1%,1/3W")
      (fields (field (name "INTERNAL_PART_NUMBER") "MCD-02234") (field (name "MANUFACTURER") "PANASONIC"))
      (libsource (lib "MCD_PARTS_database") (part "Resistor"))
    )
    (comp (ref "R51")
      (value "33mR")
      (footprint "MCD_PARTS:R0603")
      (description "Resistor, 33mR, 0603, +/-1%, 1/4W")
      (fields (field (name "INTERNAL_PART_NUMBER") "MCD-03229") (field (name "MANUFACTURER") "PANASONIC"))
      (libsource (lib "MCD_PARTS_database") (part "Resistor"))
    )
    (comp (ref "R52")
      (value "0R")
      (footprint "MCD_PARTS:R0402")
      (description "Resistor,0R,0402,5%,1/16W")
      (fields
        (field (name "INTERNAL_PART_NUMBER") "MCD-00052")
        (field (name "MANUFACTURER_PART_NUMBER") "RC0402JR-070RL")
      )
      (libsource (lib "MCD_PARTS_database") (part "Resistor"))
    )
    (comp (ref "R53")
      (value "0R")
      (footprint "MCD_PARTS:R0603")
      (description "Resistor,0R,0603,ULO")
      (fields
        (field (name "INTERNAL_PART_NUMBER") "MCD-00181")
        (field (name "MANUFACTURER_PART_NUMBER") "PMR03EZPJ000")
        (field (name "PROVIDED_BY") "SUBCO")
      )
      (libsource (lib "MCD_PARTS_database") (part "Resistor"))
    )
    (comp (ref "R54")
      (value "330mR")
      (footprint "MCD_PARTS:R0603")
      (description "Resistor, 330mR, 0603, +/-1%, 1/5W")
      (fields (field (name "INTERNAL_PART_NUMBER") "MCD-03197") (field (name "MANUFACTURER") "YAGEO"))
      (libsource (lib "MCD_PARTS_database") (part "Resistor"))
    )
    (comp (ref "R55")
      (value "0R")
      (footprint "MCD_PARTS:R0603")
      (description "Resistor,0R,0603,5%,1/10W")
      (fields
        (field (name "INTERNAL_PART_NUMBER") "MCD-00056")
        (field (name "MANUFACTURER_PART_NUMBER") "RC0603JR-070RL")
      )
      (libsource (lib "MCD_PARTS_database") (part "Resistor"))
    )
    (comp (ref "R56")
      (value "0R")
      (footprint "MCD_PARTS:R0603")
      (description "Resistor,0R,0603,5%,1/10W")
      (fields
        (field (name "INTERNAL_PART_NUMBER") "MCD-00056")
        (field (name "MANUFACTURER_PART_NUMBER") "RC0603JR-070RL")
      )
      (libsource (lib "MCD_PARTS_database") (part "Resistor"))
    )
    (comp (ref "R57")
      (value "0R")
      (footprint "MCD_PARTS:R0402")
      (description "Resistor,0R,0402,5%,1/16W")
      (fields
        (field (name "INTERNAL_PART_NUMBER") "MCD-00052")
        (field (name "MANUFACTURER_PART_NUMBER") "RC0402JR-070RL")
      )
      (libsource (lib "MCD_PARTS_database") (part "Resistor"))
    )
    (comp (ref "R58")
      (value "0R")
      (footprint "MCD_PARTS:R0603")
      (description "Resistor, 0R, 0603, +/- 0.5mR, 1/4W")
      (fields (field (name "INTERNAL_PART_NUMBER") "MCD-00181") (field (name "MANUFACTURER") "ROHM"))
      (libsource (lib "MCD_PARTS_database") (part "Resistor"))
    )
    (comp (ref "R59")
      (value "0R")
      (footprint "MCD_PARTS:R0402")
      (description "Resistor,0R,0402,5%,1/16W")
      (fields
        (field (name "INTERNAL_PART_NUMBER") "MCD-00052")
        (field (name "MANUFACTURER_PART_NUMBER") "RC0402JR-070RL")
        (field (name "PROVIDED_BY") "SUBCO")
      )
      (libsource (lib "MCD_PARTS_database") (part "Resistor"))
    )
    (comp (ref "R60")
      (value "0R")
      (footprint "MCD_PARTS:R0402")
      (description "Resistor,0R,0402,5%,1/16W")
      (fields
        (field (name "INTERNAL_PART_NUMBER") "MCD-00052")
        (field (name "MANUFACTURER_PART_NUMBER") "RC0402JR-070RL")
        (field (name "PROVIDED_BY") "SUBCO")
      )
      (libsource (lib "MCD_PARTS_database") (part "Resistor"))
    )
    (comp (ref "R61")
      (value "0R")
      (footprint "MCD_PARTS:R0402")
      (description "Resistor,0R,0402,5%,1/16W")
      (fields
        (field (name "INTERNAL_PART_NUMBER") "MCD-00052")
        (field (name "MANUFACTURER_PART_NUMBER") "RC0402JR-070RL")
        (field (name "PROVIDED_BY") "SUBCO")
      )
      (libsource (lib "MCD_PARTS_database") (part "Resistor"))
    )
    (comp (ref "R62")
      (value "82K")
      (footprint "MCD_PARTS:R0402")
      (description "Resistor, 82K, 0402, +/-1%, 1/16W")
      (fields (field (name "INTERNAL_PART_NUMBER") "MCD-00531") (field (name "MANUFACTURER") "YAGEO"))
      (libsource (lib "MCD_PARTS_database") (part "Resistor"))
    )
    (comp (ref "R65")
      (value "19K6")
      (footprint "MCD_PARTS:R0402")
      (description "Resistor, 19K6, 0402, +/-1%, 1/16W")
      (fields (field (name "INTERNAL_PART_NUMBER") "MCD-00344") (field (name "MANUFACTURER") "YAGEO"))
      (libsource (lib "MCD_PARTS_database") (part "Resistor"))
    )
    (comp (ref "R69")
      (value "0R")
      (footprint "MCD_PARTS:R0603")
      (description "Resistor,0R,0603,5%,1/10W")
      (fields
        (field (name "INTERNAL_PART_NUMBER") "MCD-00056")
        (field (name "MANUFACTURER_PART_NUMBER") "RC0603JR-070RL")
      )
      (libsource (lib "MCD_PARTS_database") (part "Resistor"))
    )
    (comp (ref "R204")
      (value "20K")
      (footprint "MCD_PARTS:R0402")
      (description "Resistor,20K,0402,1%,1/16W")
      (fields (field (name "INTERNAL_PART_NUMBER") "MCD-00421") (field (name "MANUFACTURER") "YAGEO"))
      (libsource (lib "MCD_PARTS_database") (part "Resistor"))
    )
    (comp (ref "R208")
      (value "110K")
      (footprint "MCD_PARTS:R0402")
      (description "Resistor,110K,0402,1%,1/16W")
      (fields
        (field (name "INTERNAL_PART_NUMBER") "MCD-00367")
        (field (name "MANUFACTURER_PART_NUMBER") "RC0402FR-07110KL")
      )
      (libsource (lib "MCD_PARTS_database") (part "Resistor"))
    )
    (comp (ref "R210")
      (value "270R")
      (footprint "MCD_PARTS:R0402")
      (description "Resistor,270R,0402,1%,1/16W")
      (fields
        (field (name "INTERNAL_PART_NUMBER") "MCD-00441")
        (field (name "MANUFACTURER_PART_NUMBER") "RC0402FR-07270RL")
        (field (name "PROVIDED_BY") "SUBCO")
      )
      (libsource (lib "MCD_PARTS_database") (part "Resistor"))
    )
    (comp (ref "TP8")
      (value "TP")
      (footprint "MCD_PARTS:TP_PTH-1P02MM_TEST-TERMINAL_RS_101-2391_BLACK")
      (description "Vero Technologies 1.02mm Black Terminal Post")
      (fields
        (field (name "INTERNAL_PART_NUMBER") "MCD-00713")
        (field (name "MANUFACTURER_PART_NUMBER") "20-2137")
      )
      (libsource (lib "MCD_PARTS_database") (part "Test_pin_conn_black"))
    )
    (comp (ref "U26")
      (value "STPMIC25A")
      (footprint "MCD_PARTS:ICC_QFN56-EPAD_6P5X6P5_P040")
      (description "STPMIC2")
      (fields
        (field (name "INTERNAL_PART_NUMBER") "MCD-03000")
        (field (name "MANUFACTURER") "STMICROELECTRONICS")
      )
      (libsource (lib "MCD_PARTS_database") (part "STPMIC2"))
    )
    (comp (ref "U30")
      (value "ST1L05BPUR")
      (footprint "MCD_PARTS:ICC_DFN6-EPAD_3X3_P095")
      (description "LDO Linear Voltage Regulator IC Positive Adjustable 1 Output Adjustable 1.3A 6-DFN (3x3)")
      (fields (field (name "INTERNAL_PART_NUMBER") "MCD-00581") (field (name "BMS_PART_NUMBER") "9176239"))
      (libsource (lib "MCD_PARTS_database") (part "ST1L05BPUR"))
    )
    (comp (ref "U37")
      (value "ST1S40IPUR")
      (footprint "MCD_PARTS:ICC_VFQFPN8-EPAD_4X4_P080")
      (description "3 A DC step-down switching regulator")
      (fields
        (field (name "INTERNAL_PART_NUMBER") "MCD-02219")
        (field (name "MANUFACTURER") "STMICROELECTRONICS")
      )
      (libsource (lib "MCD_PARTS_database") (part "ST1S40IPUR"))
    )
  )
  (nets
    (net (code "1") (name "/I2C7.SCL") (class "Default")
      (node (ref "U26") (pin "33") (pinfunction "SCL_33") (pintype "passive"))
    )
    (net (code "2") (name "/I2C7.SDA") (class "Default")
      (node (ref "U26") (pin "34") (pinfunction "SDA_34") (pintype "passive"))
    )
    (net (code "3") (name "/I_SENS_1V8_N") (class "Default")
      (node (ref "C19") (pin "1") (pinfunction "1_1") (pintype "passive"))
      (node (ref "CN10") (pin "14") (pinfunction "14_14") (pintype "passive"))
      (node (ref "LNK3") (pin "1") (pinfunction "1_1") (pintype "passive"))
      (node (ref "R41") (pin "2") (pinfunction "2_2") (pintype "passive"))
    )
    (net (code "4") (name "/I_SENS_VDDCORE_N") (class "Default")
      (node (ref "C20") (pin "1") (pinfunction "1_1") (pintype "passive"))
      (node (ref "CN10") (pin "6") (pinfunction "6_6") (pintype "passive"))
      (node (ref "LNK5") (pin "2") (pinfunction "2_2") (pintype "passive"))
      (node (ref "R42") (pin "2") (pinfunction "2_2") (pintype "passive"))
    )
    (net (code "5") (name "/I_SENS_VDDCPU_N") (class "Default")
      (node (ref "C25") (pin "1") (pinfunction "1_1") (pintype "passive"))
      (node (ref "CN10") (pin "4") (pinfunction "4_4") (pintype "passive"))
      (node (ref "LNK6") (pin "2") (pinfunction "2_2") (pintype "passive"))
      (node (ref "R43") (pin "2") (pinfunction "2_2") (pintype "passive"))
    )
    (net (code "6") (name "/I_SENS_VDDGPU_N") (class "Default")
      (node (ref "C33") (pin "1") (pinfunction "1_1") (pintype "passive"))
      (node (ref "CN10") (pin "10") (pinfunction "10_10") (pintype "passive"))
      (node (ref "LNK10") (pin "2") (pinfunction "2_2") (pintype "passive"))
      (node (ref "R51") (pin "2") (pinfunction "2_2") (pintype "passive"))
    )
    (net (code "7") (name "/I_SENS_VDDIO_N") (class "Default")
      (node (ref "C55") (pin "1") (pinfunction "1_1") (pintype "passive"))
      (node (ref "CN10") (pin "2") (pinfunction "2_2") (pintype "passive"))
      (node (ref "LNK12") (pin "1") (pinfunction "1_1") (pintype "passive"))
      (node (ref "R54") (pin "2") (pinfunction "2_2") (pintype "passive"))
    )
    (net (code "8") (name "/I_SENS_VDD_DDR_N") (class "Default")
      (node (ref "C31") (pin "1") (pinfunction "1_1") (pintype "passive"))
      (node (ref "CN10") (pin "12") (pinfunction "12_12") (pintype "passive"))
      (node (ref "LNK9") (pin "1") (pinfunction "1_1") (pintype "passive"))
      (node (ref "R48") (pin "2") (pinfunction "2_2") (pintype "passive"))
    )
    (net (code "9") (name "/NRST") (class "Default")
      (node (ref "R38") (pin "1") (pinfunction "1_1") (pintype "passive"))
    )
    (net (code "10") (name "/NRSTC1MS") (class "Default")
      (node (ref "R59") (pin "1") (pinfunction "1_1") (pintype "passive"))
    )
    (net (code "11") (name "/PA0_WKUP") (class "Default")
      (node (ref "U26") (pin "32") (pinfunction "INTn_32") (pintype "passive"))
    )
    (net (code "12") (name "/PWR_CPU_ON") (class "Default")
      (node (ref "R60") (pin "1") (pinfunction "1_1") (pintype "passive"))
    )
    (net (code "13") (name "/PWR_ON") (class "Default")
      (node (ref "R61") (pin "1") (pinfunction "1_1") (pintype "passive"))
    )
    (net (code "14") (name "/WAKEUPn") (class "Default")
      (node (ref "R46") (pin "1") (pinfunction "1_1") (pintype "passive"))
    )
    (net (code "15") (name "1V5_PCIE") (class "Default")
      (node (ref "R69") (pin "2") (pinfunction "2_2") (pintype "passive"))
    )
    (net (code "16") (name "1V8") (class "Default")
      (node (ref "LNK1") (pin "2") (pinfunction "2_2") (pintype "passive"))
      (node (ref "LNK3") (pin "2") (pinfunction "2_2") (pintype "passive"))
      (node (ref "R35") (pin "2") (pinfunction "2_2") (pintype "passive"))
    )
    (net (code "17") (name "1V8_1") (class "Default")
      (node (ref "C16") (pin "2") (pinfunction "2_2") (pintype "passive"))
      (node (ref "C17") (pin "2") (pinfunction "2_2") (pintype "passive"))
      (node (ref "C18") (pin "2") (pinfunction "2_2") (pintype "passive"))
      (node (ref "C19") (pin "2") (pinfunction "2_2") (pintype "passive"))
      (node (ref "CN10") (pin "13") (pinfunction "13_13") (pintype "passive"))
      (node (ref "L1") (pin "2") (pinfunction "2_2") (pintype "passive"))
      (node (ref "R35") (pin "1") (pinfunction "1_1") (pintype "passive"))
      (node (ref "R41") (pin "1") (pinfunction "1_1") (pintype "passive"))
    )
    (net (code "18") (name "1V8_FB") (class "Default")
      (node (ref "LNK1") (pin "1") (pinfunction "1_1") (pintype "passive"))
      (node (ref "U26") (pin "35") (pinfunction "VOUT5_35") (pintype "passive"))
    )
    (net (code "19") (name "3V3") (class "Default")
      (node (ref "C57") (pin "2") (pinfunction "2_2") (pintype "passive"))
      (node (ref "C58") (pin "2") (pinfunction "2_2") (pintype "passive"))
      (node (ref "C59") (pin "2") (pinfunction "2_2") (pintype "passive"))
      (node (ref "C60") (pin "2") (pinfunction "2_2") (pintype "passive"))
      (node (ref "L7") (pin "2") (pinfunction "2_2") (pintype "passive"))
      (node (ref "R55") (pin "1") (pinfunction "1_1") (pintype "passive"))
      (node (ref "R57") (pin "1") (pinfunction "1_1") (pintype "passive"))
      (node (ref "U26") (pin "53") (pinfunction "VOUT7_53") (pintype "passive"))
    )
    (net (code "20") (name "5V_STLK") (class "Default")
      (node (ref "JP4") (pin "1") (pinfunction "1_1") (pintype "passive"))
    )
    (net (code "21") (name "5V_VIN") (class "Default")
      (node (ref "C147") (pin "1") (pinfunction "1_1") (pintype "passive"))
      (node (ref "C29") (pin "2") (pinfunction "2_2") (pintype "passive"))
      (node (ref "C30") (pin "2") (pinfunction "2_2") (pintype "passive"))
      (node (ref "C32") (pin "2") (pinfunction "2_2") (pintype "passive"))
      (node (ref "C38") (pin "2") (pinfunction "2_2") (pintype "passive"))
      (node (ref "C42") (pin "1") (pinfunction "1_1") (pintype "passive"))
      (node (ref "C45") (pin "2") (pinfunction "2_2") (pintype "passive"))
      (node (ref "C46") (pin "2") (pinfunction "2_2") (pintype "passive"))
      (node (ref "C56") (pin "2") (pinfunction "2_2") (pintype "passive"))
      (node (ref "C64") (pin "2") (pinfunction "2_2") (pintype "passive"))
      (node (ref "C67") (pin "2") (pinfunction "2_2") (pintype "passive"))
      (node (ref "C68") (pin "2") (pinfunction "2_2") (pintype "passive"))
      (node (ref "JP4") (pin "2") (pinfunction "2_2") (pintype "passive"))
      (node (ref "R210") (pin "2") (pinfunction "2_2") (pintype "passive"))
      (node (ref "R56") (pin "1") (pinfunction "1_1") (pintype "passive"))
      (node (ref "U26") (pin "11") (pinfunction "VIN_11") (pintype "passive"))
      (node (ref "U26") (pin "15") (pinfunction "LDO12IN_15") (pintype "passive"))
      (node (ref "U26") (pin "20") (pinfunction "BUCK4IN_20") (pintype "passive"))
      (node (ref "U26") (pin "24") (pinfunction "BUCK3IN_24") (pintype "passive"))
      (node (ref "U26") (pin "25") (pinfunction "BUCK2IN_25") (pintype "passive"))
      (node (ref "U26") (pin "38") (pinfunction "BUCK5IN_38") (pintype "passive"))
      (node (ref "U26") (pin "39") (pinfunction "BUCK1IN_39") (pintype "passive"))
      (node (ref "U26") (pin "49") (pinfunction "BUCK6IN_49") (pintype "passive"))
      (node (ref "U26") (pin "50") (pinfunction "BUCK7IN_50") (pintype "passive"))
      (node (ref "U26") (pin "6") (pinfunction "LDO56IN_6") (pintype "passive"))
    )
    (net (code "22") (name "GND") (class "Default")
      (node (ref "B2") (pin "1") (pinfunction "1_1") (pintype "passive"))
      (node (ref "B2") (pin "2") (pinfunction "2_2") (pintype "passive"))
      (node (ref "C114") (pin "1") (pinfunction "1_1") (pintype "passive"))
      (node (ref "C116") (pin "1") (pinfunction "1_1") (pintype "passive"))
      (node (ref "C117") (pin "1") (pinfunction "1_1") (pintype "passive"))
      (node (ref "C118") (pin "1") (pinfunction "1_1") (pintype "passive"))
      (node (ref "C127") (pin "2") (pinfunction "2_2") (pintype "passive"))
      (node (ref "C130") (pin "1") (pinfunction "1_1") (pintype "passive"))
      (node (ref "C147") (pin "2") (pinfunction "2_2") (pintype "passive"))
      (node (ref "C148") (pin "1") (pinfunction "1_1") (pintype "passive"))
      (node (ref "C16") (pin "1") (pinfunction "1_1") (pintype "passive"))
      (node (ref "C17") (pin "1") (pinfunction "1_1") (pintype "passive"))
      (node (ref "C18") (pin "1") (pinfunction "1_1") (pintype "passive"))
      (node (ref "C21") (pin "1") (pinfunction "1_1") (pintype "passive"))
      (node (ref "C22") (pin "1") (pinfunction "1_1") (pintype "passive"))
      (node (ref "C23") (pin "1") (pinfunction "1_1") (pintype "passive"))
      (node (ref "C24") (pin "1") (pinfunction "1_1") (pintype "passive"))
      (node (ref "C26") (pin "1") (pinfunction "1_1") (pintype "passive"))
      (node (ref "C27") (pin "1") (pinfunction "1_1") (pintype "passive"))
      (node (ref "C28") (pin "1") (pinfunction "1_1") (pintype "passive"))
      (node (ref "C29") (pin "1") (pinfunction "1_1") (pintype "passive"))
      (node (ref "C30") (pin "1") (pinfunction "1_1") (pintype "passive"))
      (node (ref "C32") (pin "1") (pinfunction "1_1") (pintype "passive"))
      (node (ref "C34") (pin "1") (pinfunction "1_1") (pintype "passive"))
      (node (ref "C35") (pin "1") (pinfunction "1_1") (pintype "passive"))
      (node (ref "C36") (pin "1") (pinfunction "1_1") (pintype "passive"))
      (node (ref "C37") (pin "1") (pinfunction "1_1") (pintype "passive"))
      (node (ref "C38") (pin "1") (pinfunction "1_1") (pintype "passive"))
      (node (ref "C39") (pin "1") (pinfunction "1_1") (pintype "passive"))
      (node (ref "C40") (pin "1") (pinfunction "1_1") (pintype "passive"))
      (node (ref "C41") (pin "1") (pinfunction "1_1") (pintype "passive"))
      (node (ref "C42") (pin "2") (pinfunction "2_2") (pintype "passive"))
      (node (ref "C43") (pin "2") (pinfunction "2_2") (pintype "passive"))
      (node (ref "C44") (pin "1") (pinfunction "1_1") (pintype "passive"))
      (node (ref "C45") (pin "1") (pinfunction "1_1") (pintype "passive"))
      (node (ref "C46") (pin "1") (pinfunction "1_1") (pintype "passive"))
      (node (ref "C47") (pin "1") (pinfunction "1_1") (pintype "passive"))
      (node (ref "C5") (pin "1") (pinfunction "1_1") (pintype "passive"))
      (node (ref "C52") (pin "1") (pinfunction "1_1") (pintype "passive"))
      (node (ref "C53") (pin "1") (pinfunction "1_1") (pintype "passive"))
      (node (ref "C54") (pin "1") (pinfunction "1_1") (pintype "passive"))
      (node (ref "C56") (pin "1") (pinfunction "1_1") (pintype "passive"))
      (node (ref "C57") (pin "1") (pinfunction "1_1") (pintype "passive"))
      (node (ref "C58") (pin "1") (pinfunction "1_1") (pintype "passive"))
      (node (ref "C59") (pin "1") (pinfunction "1_1") (pintype "passive"))
      (node (ref "C60") (pin "1") (pinfunction "1_1") (pintype "passive"))
      (node (ref "C61") (pin "1") (pinfunction "1_1") (pintype "passive"))
      (node (ref "C63") (pin "2") (pinfunction "2_2") (pintype "passive"))
      (node (ref "C64") (pin "1") (pinfunction "1_1") (pintype "passive"))
      (node (ref "C65") (pin "2") (pinfunction "2_2") (pintype "passive"))
      (node (ref "C66") (pin "1") (pinfunction "1_1") (pintype "passive"))
      (node (ref "C67") (pin "1") (pinfunction "1_1") (pintype "passive"))
      (node (ref "C68") (pin "1") (pinfunction "1_1") (pintype "passive"))
      (node (ref "C70") (pin "1") (pinfunction "1_1") (pintype "passive"))
      (node (ref "C71") (pin "1") (pinfunction "1_1") (pintype "passive"))
      (node (ref "C72") (pin "2") (pinfunction "2_2") (pintype "passive"))
      (node (ref "C73") (pin "2") (pinfunction "2_2") (pintype "passive"))
      (node (ref "C74") (pin "2") (pinfunction "2_2") (pintype "passive"))
      (node (ref "C75") (pin "2") (pinfunction "2_2") (pintype "passive"))
      (node (ref "C76") (pin "1") (pinfunction "1_1") (pintype "passive"))
      (node (ref "C89") (pin "1") (pinfunction "1_1") (pintype "passive"))
      (node (ref "CN10") (pin "7") (pinfunction "7_7") (pintype "passive"))
      (node (ref "CN10") (pin "8") (pinfunction "8_8") (pintype "passive"))
      (node (ref "CN20") (pin "2") (pintype "passive"))
      (node (ref "CN20") (pin "3") (pintype "passive"))
      (node (ref "LD11") (pin "2") (pintype "passive"))
      (node (ref "R204") (pin "1") (pinfunction "1_1") (pintype "passive"))
      (node (ref "R62") (pin "1") (pinfunction "1_1") (pintype "passive"))
      (node (ref "TP8") (pin "1") (pinfunction "1_1") (pintype "passive"))
      (node (ref "U26") (pin "10") (pinfunction "AGND_10") (pintype "passive"))
      (node (ref "U26") (pin "18") (pinfunction "PGND4_18") (pintype "passive"))
      (node (ref "U26") (pin "22") (pinfunction "PGND3_22") (pintype "passive"))
      (node (ref "U26") (pin "27") (pinfunction "PGND2_27") (pintype "passive"))
      (node (ref "U26") (pin "36") (pinfunction "PGND5_36") (pintype "passive"))
      (node (ref "U26") (pin "41") (pinfunction "PGND1_41") (pintype "passive"))
      (node (ref "U26") (pin "47") (pinfunction "PGND6_47") (pintype "passive"))
      (node (ref "U26") (pin "52") (pinfunction "PGND7_52") (pintype "passive"))
      (node (ref "U26") (pin "57") (pinfunction "GND_57") (pintype "passive"))
      (node (ref "U26") (pin "9") (pinfunction "GNDLDO_9") (pintype "passive"))
      (node (ref "U30") (pin "2") (pinfunction "GND_2") (pintype "passive"))
      (node (ref "U30") (pin "EP") (pinfunction "GND_EP") (pintype "passive"))
      (node (ref "U37") (pin "4") (pinfunction "GND_4") (pintype "passive"))
      (node (ref "U37") (pin "8") (pinfunction "PGND_8") (pintype "passive"))
      (node (ref "U37") (pin "9") (pinfunction "EPAD_9") (pintype "passive"))
    )
    (net (code "23") (name "Net-(C114-Pad2)") (class "Default")
      (node (ref "C114") (pin "2") (pinfunction "2_2") (pintype "passive"))
      (node (ref "C118") (pin "2") (pinfunction "2_2") (pintype "passive"))
      (node (ref "C151") (pin "1") (pinfunction "1_1") (pintype "passive"))
      (node (ref "JP4") (pin "3") (pinfunction "3_3") (pintype "passive"))
      (node (ref "L8") (pin "2") (pinfunction "2_2") (pintype "passive"))
      (node (ref "R208") (pin "1") (pinfunction "1_1") (pintype "passive"))
    )
    (net (code "24") (name "Net-(LD11-Pad1)") (class "Default")
      (node (ref "LD11") (pin "1") (pintype "passive"))
      (node (ref "R210") (pin "1") (pinfunction "1_1") (pintype "passive"))
    )
    (net (code "25") (name "Net-(U26-INTLDO)") (class "Default")
      (node (ref "C75") (pin "1") (pinfunction "1_1") (pintype "passive"))
      (node (ref "U26") (pin "8") (pinfunction "INTLDO_8") (pintype "passive"))
    )
    (net (code "26") (name "Net-(U26-LDO1OUT)") (class "Default")
      (node (ref "C66") (pin "2") (pinfunction "2_2") (pintype "passive"))
      (node (ref "R58") (pin "1") (pinfunction "1_1") (pintype "passive"))
      (node (ref "U26") (pin "14") (pinfunction "LDO1OUT_14") (pintype "passive"))
    )
    (net (code "27") (name "Net-(U26-LDO78IN)") (class "Default")
      (node (ref "C70") (pin "2") (pinfunction "2_2") (pintype "passive"))
      (node (ref "R56") (pin "2") (pinfunction "2_2") (pintype "passive"))
      (node (ref "R57") (pin "2") (pinfunction "2_2") (pintype "passive"))
      (node (ref "U26") (pin "3") (pinfunction "LDO78IN_3") (pintype "passive"))
    )
    (net (code "28") (name "Net-(U26-PONKEYn)") (class "Default")
      (node (ref "B2") (pin "3") (pinfunction "3_3") (pintype "passive"))
      (node (ref "B2") (pin "4") (pinfunction "4_4") (pintype "passive"))
      (node (ref "C5") (pin "2") (pinfunction "2_2") (pintype "passive"))
      (node (ref "U26") (pin "1") (pinfunction "PONKEYn_1") (pintype "passive"))
    )
    (net (code "29") (name "Net-(U26-PWRCTRL1)") (class "Default")
      (node (ref "R61") (pin "2") (pinfunction "2_2") (pintype "passive"))
      (node (ref "U26") (pin "56") (pinfunction "PWRCTRL1_56") (pintype "passive"))
    )
    (net (code "30") (name "Net-(U26-PWRCTRL2)") (class "Default")
      (node (ref "R60") (pin "2") (pinfunction "2_2") (pintype "passive"))
      (node (ref "U26") (pin "55") (pinfunction "PWRCTRL2_55") (pintype "passive"))
    )
    (net (code "31") (name "Net-(U26-PWRCTRL3)") (class "Default")
      (node (ref "R59") (pin "2") (pinfunction "2_2") (pintype "passive"))
      (node (ref "U26") (pin "54") (pinfunction "PWRCTRL3_54") (pintype "passive"))
    )
    (net (code "32") (name "Net-(U26-REFDDR)") (class "Default")
      (node (ref "C43") (pin "1") (pinfunction "1_1") (pintype "passive"))
      (node (ref "R52") (pin "1") (pinfunction "1_1") (pintype "passive"))
      (node (ref "U26") (pin "45") (pinfunction "REFDDR_45") (pintype "passive"))
    )
    (net (code "33") (name "Net-(U26-RSTn)") (class "Default")
      (node (ref "R38") (pin "2") (pinfunction "2_2") (pintype "passive"))
      (node (ref "U26") (pin "31") (pinfunction "RSTn_31") (pintype "passive"))
    )
    (net (code "34") (name "Net-(U26-VBUS)") (class "Default")
      (node (ref "C71") (pin "2") (pinfunction "2_2") (pintype "passive"))
      (node (ref "U26") (pin "12") (pinfunction "VBUS_12") (pintype "passive"))
    )
    (net (code "35") (name "Net-(U26-VLX1)") (class "Default")
      (node (ref "L3") (pin "1") (pinfunction "1_1") (pintype "passive"))
      (node (ref "U26") (pin "40") (pinfunction "VLX1_40") (pintype "passive"))
    )
    (net (code "36") (name "Net-(U26-VLX2)") (class "Default")
      (node (ref "L2") (pin "1") (pinfunction "1_1") (pintype "passive"))
      (node (ref "U26") (pin "26") (pinfunction "VLX2_26") (pintype "passive"))
    )
    (net (code "37") (name "Net-(U26-VLX3)") (class "Default")
      (node (ref "L4") (pin "1") (pinfunction "1_1") (pintype "passive"))
      (node (ref "U26") (pin "23") (pinfunction "VLX3_23") (pintype "passive"))
    )
    (net (code "38") (name "Net-(U26-VLX4)") (class "Default")
      (node (ref "L6") (pin "1") (pinfunction "1_1") (pintype "passive"))
      (node (ref "U26") (pin "19") (pinfunction "VLX4_19") (pintype "passive"))
    )
    (net (code "39") (name "Net-(U26-VLX5)") (class "Default")
      (node (ref "L1") (pin "1") (pinfunction "1_1") (pintype "passive"))
      (node (ref "U26") (pin "37") (pinfunction "VLX5_37") (pintype "passive"))
    )
    (net (code "40") (name "Net-(U26-VLX6)") (class "Default")
      (node (ref "L5") (pin "1") (pinfunction "1_1") (pintype "passive"))
      (node (ref "U26") (pin "48") (pinfunction "VLX6_48") (pintype "passive"))
    )
    (net (code "41") (name "Net-(U26-VLX7)") (class "Default")
      (node (ref "L7") (pin "1") (pinfunction "1_1") (pintype "passive"))
      (node (ref "U26") (pin "51") (pinfunction "VLX7_51") (pintype "passive"))
    )
    (net (code "42") (name "Net-(U26-WAKEUPn)") (class "Default")
      (node (ref "R46") (pin "2") (pinfunction "2_2") (pintype "passive"))
      (node (ref "U26") (pin "30") (pinfunction "WAKEUPn_30") (pintype "passive"))
    )
    (net (code "43") (name "Net-(U30-ADJ)") (class "Default")
      (node (ref "R62") (pin "2") (pinfunction "2_2") (pintype "passive"))
      (node (ref "R65") (pin "1") (pinfunction "1_1") (pintype "passive"))
      (node (ref "U30") (pin "5") (pinfunction "ADJ_5") (pintype "passive"))
    )
    (net (code "44") (name "Net-(U30-EN)") (class "Default")
      (node (ref "C76") (pin "2") (pinfunction "2_2") (pintype "passive"))
      (node (ref "R55") (pin "2") (pinfunction "2_2") (pintype "passive"))
      (node (ref "U30") (pin "1") (pinfunction "EN_1") (pintype "passive"))
      (node (ref "U30") (pin "6") (pinfunction "VI_6") (pintype "passive"))
    )
    (net (code "45") (name "Net-(U30-VO)") (class "Default")
      (node (ref "C89") (pin "2") (pinfunction "2_2") (pintype "passive"))
      (node (ref "R65") (pin "2") (pinfunction "2_2") (pintype "passive"))
      (node (ref "R69") (pin "1") (pinfunction "1_1") (pintype "passive"))
      (node (ref "U30") (pin "4") (pinfunction "VO_4") (pintype "passive"))
    )
    (net (code "46") (name "Net-(U37-EN)") (class "Default")
      (node (ref "C116") (pin "2") (pinfunction "2_2") (pintype "passive"))
      (node (ref "C117") (pin "2") (pinfunction "2_2") (pintype "passive"))
      (node (ref "C127") (pin "1") (pinfunction "1_1") (pintype "passive"))
      (node (ref "C130") (pin "2") (pinfunction "2_2") (pintype "passive"))
      (node (ref "C148") (pin "2") (pinfunction "2_2") (pintype "passive"))
      (node (ref "F1") (pin "2") (pinfunction "2_2") (pintype "passive"))
      (node (ref "U37") (pin "1") (pinfunction "VINA_1") (pintype "passive"))
      (node (ref "U37") (pin "2") (pinfunction "EN_2") (pintype "passive"))
      (node (ref "U37") (pin "6") (pinfunction "VINSW_6") (pintype "passive"))
    )
    (net (code "47") (name "Net-(U37-FB)") (class "Default")
      (node (ref "C151") (pin "2") (pinfunction "2_2") (pintype "passive"))
      (node (ref "R204") (pin "2") (pinfunction "2_2") (pintype "passive"))
      (node (ref "R208") (pin "2") (pinfunction "2_2") (pintype "passive"))
      (node (ref "U37") (pin "3") (pinfunction "FB_3") (pintype "passive"))
    )
    (net (code "48") (name "Net-(U37-SW)") (class "Default")
      (node (ref "L8") (pin "1") (pinfunction "1_1") (pintype "passive"))
      (node (ref "U37") (pin "7") (pinfunction "SW_7") (pintype "passive"))
    )
    (net (code "49") (name "VDD3V3_USB") (class "Default")
      (node (ref "C61") (pin "2") (pinfunction "2_2") (pintype "passive"))
      (node (ref "U26") (pin "13") (pinfunction "LDO4OUT_13") (pintype "passive"))
    )
    (net (code "50") (name "VDDA1V8_AON") (class "Default")
      (node (ref "R58") (pin "2") (pinfunction "2_2") (pintype "passive"))
    )
    (net (code "51") (name "VDDCORE") (class "Default")
      (node (ref "LNK2") (pin "2") (pinfunction "2_2") (pintype "passive"))
      (node (ref "LNK5") (pin "1") (pinfunction "1_1") (pintype "passive"))
      (node (ref "R36") (pin "2") (pinfunction "2_2") (pintype "passive"))
    )
    (net (code "52") (name "VDDCORE_1") (class "Default")
      (node (ref "C20") (pin "2") (pinfunction "2_2") (pintype "passive"))
      (node (ref "C21") (pin "2") (pinfunction "2_2") (pintype "passive"))
      (node (ref "C22") (pin "2") (pinfunction "2_2") (pintype "passive"))
      (node (ref "C23") (pin "2") (pinfunction "2_2") (pintype "passive"))
      (node (ref "C24") (pin "2") (pinfunction "2_2") (pintype "passive"))
      (node (ref "CN10") (pin "5") (pinfunction "5_5") (pintype "passive"))
      (node (ref "L2") (pin "2") (pinfunction "2_2") (pintype "passive"))
      (node (ref "R36") (pin "1") (pinfunction "1_1") (pintype "passive"))
      (node (ref "R42") (pin "1") (pinfunction "1_1") (pintype "passive"))
    )
    (net (code "53") (name "VDDCORE_FB") (class "Default")
      (node (ref "LNK2") (pin "1") (pinfunction "1_1") (pintype "passive"))
      (node (ref "U26") (pin "28") (pinfunction "VOUT2_28") (pintype "passive"))
    )
    (net (code "54") (name "VDDCPU") (class "Default")
      (node (ref "LNK4") (pin "1") (pinfunction "1_1") (pintype "passive"))
      (node (ref "LNK6") (pin "1") (pinfunction "1_1") (pintype "passive"))
      (node (ref "R39") (pin "2") (pinfunction "2_2") (pintype "passive"))
    )
    (net (code "55") (name "VDDCPU_1") (class "Default")
      (node (ref "C25") (pin "2") (pinfunction "2_2") (pintype "passive"))
      (node (ref "C26") (pin "2") (pinfunction "2_2") (pintype "passive"))
      (node (ref "C27") (pin "2") (pinfunction "2_2") (pintype "passive"))
      (node (ref "C28") (pin "2") (pinfunction "2_2") (pintype "passive"))
      (node (ref "CN10") (pin "3") (pinfunction "3_3") (pintype "passive"))
      (node (ref "L3") (pin "2") (pinfunction "2_2") (pintype "passive"))
      (node (ref "R39") (pin "1") (pinfunction "1_1") (pintype "passive"))
      (node (ref "R43") (pin "1") (pinfunction "1_1") (pintype "passive"))
    )
    (net (code "56") (name "VDDCPU_FB") (class "Default")
      (node (ref "LNK4") (pin "2") (pinfunction "2_2") (pintype "passive"))
      (node (ref "U26") (pin "42") (pinfunction "VOUT1_42") (pintype "passive"))
    )
    (net (code "57") (name "VDDGPU") (class "Default")
      (node (ref "LNK10") (pin "1") (pinfunction "1_1") (pintype "passive"))
      (node (ref "LNK7") (pin "2") (pinfunction "2_2") (pintype "passive"))
      (node (ref "R45") (pin "2") (pinfunction "2_2") (pintype "passive"))
    )
    (net (code "58") (name "VDDGPU_1") (class "Default")
      (node (ref "C33") (pin "2") (pinfunction "2_2") (pintype "passive"))
      (node (ref "C34") (pin "2") (pinfunction "2_2") (pintype "passive"))
      (node (ref "C35") (pin "2") (pinfunction "2_2") (pintype "passive"))
      (node (ref "C36") (pin "2") (pinfunction "2_2") (pintype "passive"))
      (node (ref "C37") (pin "2") (pinfunction "2_2") (pintype "passive"))
      (node (ref "CN10") (pin "9") (pinfunction "9_9") (pintype "passive"))
      (node (ref "L4") (pin "2") (pinfunction "2_2") (pintype "passive"))
      (node (ref "R45") (pin "1") (pinfunction "1_1") (pintype "passive"))
      (node (ref "R51") (pin "1") (pinfunction "1_1") (pintype "passive"))
    )
    (net (code "59") (name "VDDGPU_FB") (class "Default")
      (node (ref "LNK7") (pin "1") (pinfunction "1_1") (pintype "passive"))
      (node (ref "U26") (pin "21") (pinfunction "VOUT3_21") (pintype "passive"))
    )
    (net (code "60") (name "VDDIO") (class "Default")
      (node (ref "LNK11") (pin "2") (pinfunction "2_2") (pintype "passive"))
      (node (ref "LNK12") (pin "2") (pinfunction "2_2") (pintype "passive"))
      (node (ref "R53") (pin "2") (pinfunction "2_2") (pintype "passive"))
      (node (ref "U26") (pin "29") (pinfunction "VIO_29") (pintype "passive"))
    )
    (net (code "61") (name "VDDIO_1") (class "Default")
      (node (ref "C52") (pin "2") (pinfunction "2_2") (pintype "passive"))
      (node (ref "C53") (pin "2") (pinfunction "2_2") (pintype "passive"))
      (node (ref "C54") (pin "2") (pinfunction "2_2") (pintype "passive"))
      (node (ref "C55") (pin "2") (pinfunction "2_2") (pintype "passive"))
      (node (ref "CN10") (pin "1") (pinfunction "1_1") (pintype "passive"))
      (node (ref "L6") (pin "2") (pinfunction "2_2") (pintype "passive"))
      (node (ref "R53") (pin "1") (pinfunction "1_1") (pintype "passive"))
      (node (ref "R54") (pin "1") (pinfunction "1_1") (pintype "passive"))
    )
    (net (code "62") (name "VDDIO_FB") (class "Default")
      (node (ref "LNK11") (pin "1") (pinfunction "1_1") (pintype "passive"))
      (node (ref "U26") (pin "17") (pinfunction "VOUT4_17") (pintype "passive"))
    )
    (net (code "63") (name "VDDIO_SDCARD") (class "Default")
      (node (ref "C63") (pin "1") (pinfunction "1_1") (pintype "passive"))
      (node (ref "U26") (pin "2") (pinfunction "LDO8OUT_2") (pintype "passive"))
    )
    (net (code "64") (name "VDD_DDR") (class "Default")
      (node (ref "C39") (pin "2") (pinfunction "2_2") (pintype "passive"))
      (node (ref "LNK8") (pin "2") (pinfunction "2_2") (pintype "passive"))
      (node (ref "LNK9") (pin "2") (pinfunction "2_2") (pintype "passive"))
      (node (ref "R47") (pin "2") (pinfunction "2_2") (pintype "passive"))
      (node (ref "U26") (pin "43") (pinfunction "LDO3IN_43") (pintype "passive"))
    )
    (net (code "65") (name "VDD_DDR_1") (class "Default")
      (node (ref "C31") (pin "2") (pinfunction "2_2") (pintype "passive"))
      (node (ref "C41") (pin "2") (pinfunction "2_2") (pintype "passive"))
      (node (ref "C44") (pin "2") (pinfunction "2_2") (pintype "passive"))
      (node (ref "C47") (pin "2") (pinfunction "2_2") (pintype "passive"))
      (node (ref "CN10") (pin "11") (pinfunction "11_11") (pintype "passive"))
      (node (ref "L5") (pin "2") (pinfunction "2_2") (pintype "passive"))
      (node (ref "R47") (pin "1") (pinfunction "1_1") (pintype "passive"))
      (node (ref "R48") (pin "1") (pinfunction "1_1") (pintype "passive"))
    )
    (net (code "66") (name "VDD_DDR_FB") (class "Default")
      (node (ref "LNK8") (pin "1") (pinfunction "1_1") (pintype "passive"))
      (node (ref "U26") (pin "46") (pinfunction "VOUT6_46") (pintype "passive"))
    )
    (net (code "67") (name "VDD_EMMC") (class "Default")
      (node (ref "C65") (pin "1") (pinfunction "1_1") (pintype "passive"))
      (node (ref "U26") (pin "16") (pinfunction "LDO2OUT_16") (pintype "passive"))
    )
    (net (code "68") (name "VDD_SDCARD") (class "Default")
      (node (ref "C72") (pin "1") (pinfunction "1_1") (pintype "passive"))
      (node (ref "U26") (pin "4") (pinfunction "LDO7OUT_4") (pintype "passive"))
    )
    (net (code "69") (name "VDD_XXXX") (class "Default")
      (node (ref "C73") (pin "1") (pinfunction "1_1") (pintype "passive"))
      (node (ref "U26") (pin "5") (pinfunction "LDO6OUT_5") (pintype "passive"))
    )
    (net (code "70") (name "VIN_JACK") (class "Default")
      (node (ref "CN20") (pin "1") (pintype "passive"))
      (node (ref "F1") (pin "1") (pinfunction "1_1") (pintype "passive"))
    )
    (net (code "71") (name "VPP_DDR") (class "Default")
      (node (ref "C74") (pin "1") (pinfunction "1_1") (pintype "passive"))
      (node (ref "U26") (pin "7") (pinfunction "LDO5OUT_7") (pintype "passive"))
    )
    (net (code "72") (name "VREF_DDR") (class "Default")
      (node (ref "R52") (pin "2") (pinfunction "2_2") (pintype "passive"))
    )
    (net (code "73") (name "VTT_DDR") (class "Default")
      (node (ref "C40") (pin "2") (pinfunction "2_2") (pintype "passive"))
      (node (ref "U26") (pin "44") (pinfunction "LDO3OUT_44") (pintype "passive"))
    )
    (net (code "74") (name "unconnected-(U30-PG-Pad3)") (class "Default")
      (node (ref "U30") (pin "3") (pinfunction "PG_3") (pintype "passive+no_connect"))
    )
    (net (code "75") (name "unconnected-(U37-NC-Pad5)") (class "Default")
      (node (ref "U37") (pin "5") (pinfunction "NC_5") (pintype "passive+no_connect"))
    )
  )
)
